# AKA-BeagleBone-ProtoBoard-v0_1.net
KiCad netlist of a schematic drawn in EAGLE
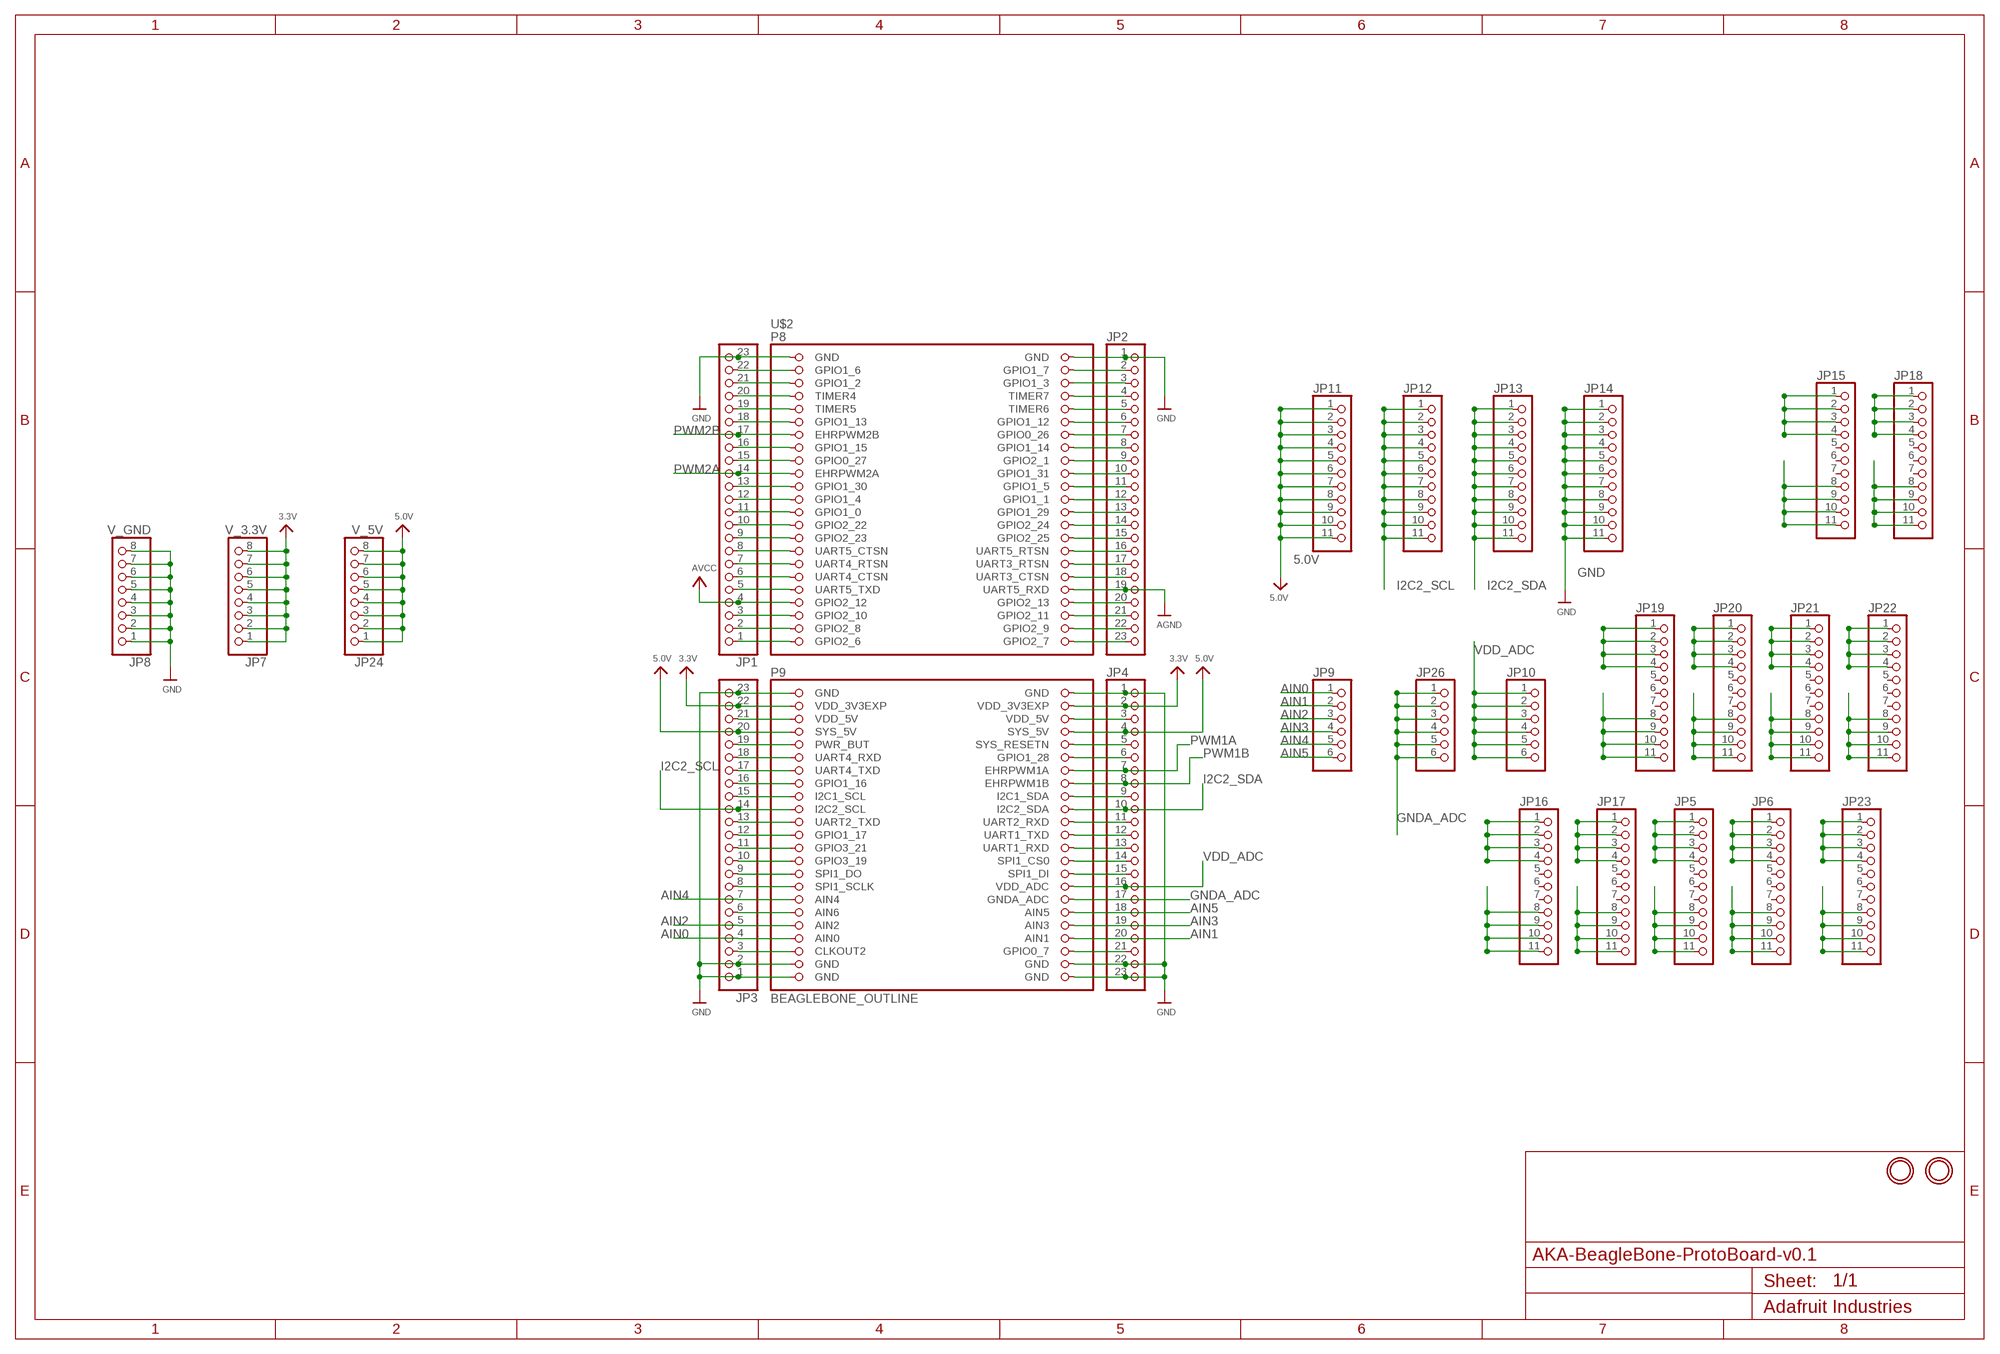
[diagram p0: schematic, sheet 1]

(export (version "E")
  (design (tool "Eeschema 10.0.6"))
  (components
    (comp (ref "JP1")
      (value "HEADER-1X23")
      (footprint "eagle-import:1X23_ROUND_70MIL")
      (libsource (lib "eagle-import") (part "HEADER-1X23"))
    )
    (comp (ref "JP2")
      (value "HEADER-1X23")
      (footprint "eagle-import:1X23_ROUND_70MIL")
      (libsource (lib "eagle-import") (part "HEADER-1X23"))
    )
    (comp (ref "JP3")
      (value "HEADER-1X23")
      (footprint "eagle-import:1X23_ROUND_70MIL")
      (libsource (lib "eagle-import") (part "HEADER-1X23"))
    )
    (comp (ref "JP4")
      (value "HEADER-1X23")
      (footprint "eagle-import:1X23_ROUND_70MIL")
      (libsource (lib "eagle-import") (part "HEADER-1X23"))
    )
    (comp (ref "JP5")
      (value "HEADER-1X1176MIL")
      (footprint "eagle-import:1X11_ROUND_76")
      (libsource (lib "eagle-import") (part "HEADER-1X1176MIL"))
    )
    (comp (ref "JP6")
      (value "HEADER-1X1176MIL")
      (footprint "eagle-import:1X11_ROUND_76")
      (libsource (lib "eagle-import") (part "HEADER-1X1176MIL"))
    )
    (comp (ref "JP7")
      (value "V_3.3V")
      (footprint "eagle-import:1X08_ROUND_70")
      (libsource (lib "eagle-import") (part "HEADER-1X870MIL"))
    )
    (comp (ref "JP8")
      (value "V_GND")
      (footprint "eagle-import:1X08_ROUND_70")
      (libsource (lib "eagle-import") (part "HEADER-1X870MIL"))
    )
    (comp (ref "JP9")
      (value "HEADER-1X676MIL")
      (footprint "eagle-import:1X06_ROUND_76")
      (libsource (lib "eagle-import") (part "HEADER-1X676MIL"))
    )
    (comp (ref "JP10")
      (value "HEADER-1X676MIL")
      (footprint "eagle-import:1X06_ROUND_76")
      (libsource (lib "eagle-import") (part "HEADER-1X676MIL"))
    )
    (comp (ref "JP11")
      (value "HEADER-1X1176MIL")
      (footprint "eagle-import:1X11_ROUND_76")
      (libsource (lib "eagle-import") (part "HEADER-1X1176MIL"))
    )
    (comp (ref "JP12")
      (value "HEADER-1X1176MIL")
      (footprint "eagle-import:1X11_ROUND_76")
      (libsource (lib "eagle-import") (part "HEADER-1X1176MIL"))
    )
    (comp (ref "JP13")
      (value "HEADER-1X1176MIL")
      (footprint "eagle-import:1X11_ROUND_76")
      (libsource (lib "eagle-import") (part "HEADER-1X1176MIL"))
    )
    (comp (ref "JP14")
      (value "HEADER-1X1176MIL")
      (footprint "eagle-import:1X11_ROUND_76")
      (libsource (lib "eagle-import") (part "HEADER-1X1176MIL"))
    )
    (comp (ref "JP15")
      (value "HEADER-1X1176MIL")
      (footprint "eagle-import:1X11_ROUND_76")
      (libsource (lib "eagle-import") (part "HEADER-1X1176MIL"))
    )
    (comp (ref "JP16")
      (value "HEADER-1X1176MIL")
      (footprint "eagle-import:1X11_ROUND_76")
      (libsource (lib "eagle-import") (part "HEADER-1X1176MIL"))
    )
    (comp (ref "JP17")
      (value "HEADER-1X1176MIL")
      (footprint "eagle-import:1X11_ROUND_76")
      (libsource (lib "eagle-import") (part "HEADER-1X1176MIL"))
    )
    (comp (ref "JP18")
      (value "HEADER-1X1176MIL")
      (footprint "eagle-import:1X11_ROUND_76")
      (libsource (lib "eagle-import") (part "HEADER-1X1176MIL"))
    )
    (comp (ref "JP19")
      (value "HEADER-1X1176MIL")
      (footprint "eagle-import:1X11_ROUND_76")
      (libsource (lib "eagle-import") (part "HEADER-1X1176MIL"))
    )
    (comp (ref "JP20")
      (value "HEADER-1X1176MIL")
      (footprint "eagle-import:1X11_ROUND_76")
      (libsource (lib "eagle-import") (part "HEADER-1X1176MIL"))
    )
    (comp (ref "JP21")
      (value "HEADER-1X1176MIL")
      (footprint "eagle-import:1X11_ROUND_76")
      (libsource (lib "eagle-import") (part "HEADER-1X1176MIL"))
    )
    (comp (ref "JP22")
      (value "HEADER-1X1176MIL")
      (footprint "eagle-import:1X11_ROUND_76")
      (libsource (lib "eagle-import") (part "HEADER-1X1176MIL"))
    )
    (comp (ref "JP23")
      (value "HEADER-1X1176MIL")
      (footprint "eagle-import:1X11_ROUND_76")
      (libsource (lib "eagle-import") (part "HEADER-1X1176MIL"))
    )
    (comp (ref "JP24")
      (value "V_5V")
      (footprint "eagle-import:1X08_ROUND_70")
      (libsource (lib "eagle-import") (part "HEADER-1X870MIL"))
    )
    (comp (ref "JP26")
      (value "HEADER-1X676MIL")
      (footprint "eagle-import:1X06_ROUND_76")
      (libsource (lib "eagle-import") (part "HEADER-1X676MIL"))
    )
    (comp (ref "U$2")
      (value "BEAGLEBONE_OUTLINE")
      (footprint "eagle-import:BEAGLEBONE_SHIELD")
      (libsource (lib "eagle-import") (part "BEAGLEBONE_OUTLINE"))
    )
    (comp (ref "U$22")
      (value "MOUNTINGHOLE3.0THIN")
      (footprint "eagle-import:MOUNTINGHOLE_3.0_PLATEDTHIN")
      (libsource (lib "eagle-import") (part "MOUNTINGHOLE3.0THIN"))
    )
    (comp (ref "U$23")
      (value "MOUNTINGHOLE3.0THIN")
      (footprint "eagle-import:MOUNTINGHOLE_3.0_PLATEDTHIN")
      (libsource (lib "eagle-import") (part "MOUNTINGHOLE3.0THIN"))
    )
  )
  (nets
    (net (code "1") (name "/AIN0") (class "Default")
      (node (ref "JP3") (pin "4") (pinfunction "4_4") (pintype "passive"))
      (node (ref "JP9") (pin "1") (pinfunction "1_1") (pintype "passive"))
      (node (ref "U$2") (pin "85") (pinfunction "AIN0_85") (pintype "power_in"))
    )
    (net (code "2") (name "/AIN1") (class "Default")
      (node (ref "JP4") (pin "20") (pinfunction "20_20") (pintype "passive"))
      (node (ref "JP9") (pin "2") (pinfunction "2_2") (pintype "passive"))
      (node (ref "U$2") (pin "86") (pinfunction "AIN1_86") (pintype "input"))
    )
    (net (code "3") (name "/AIN2") (class "Default")
      (node (ref "JP3") (pin "5") (pinfunction "5_5") (pintype "passive"))
      (node (ref "JP9") (pin "3") (pinfunction "3_3") (pintype "passive"))
      (node (ref "U$2") (pin "83") (pinfunction "AIN2_83") (pintype "passive"))
    )
    (net (code "4") (name "/AIN3") (class "Default")
      (node (ref "JP4") (pin "19") (pinfunction "19_19") (pintype "passive"))
      (node (ref "JP9") (pin "4") (pinfunction "4_4") (pintype "passive"))
      (node (ref "U$2") (pin "84") (pinfunction "AIN3_84") (pintype "power_in"))
    )
    (net (code "5") (name "/AIN4") (class "Default")
      (node (ref "JP3") (pin "7") (pinfunction "7_7") (pintype "passive"))
      (node (ref "JP9") (pin "5") (pinfunction "5_5") (pintype "passive"))
      (node (ref "U$2") (pin "79") (pinfunction "AIN4_79") (pintype "passive"))
    )
    (net (code "6") (name "/AIN5") (class "Default")
      (node (ref "JP4") (pin "18") (pinfunction "18_18") (pintype "passive"))
      (node (ref "JP9") (pin "6") (pinfunction "6_6") (pintype "passive"))
      (node (ref "U$2") (pin "82") (pinfunction "AIN5_82") (pintype "passive"))
    )
    (net (code "7") (name "/GNDA_ADC") (class "Default")
      (node (ref "JP26") (pin "1") (pinfunction "1_1") (pintype "passive"))
      (node (ref "JP26") (pin "2") (pinfunction "2_2") (pintype "passive"))
      (node (ref "JP26") (pin "3") (pinfunction "3_3") (pintype "passive"))
      (node (ref "JP26") (pin "4") (pinfunction "4_4") (pintype "passive"))
      (node (ref "JP26") (pin "5") (pinfunction "5_5") (pintype "passive"))
      (node (ref "JP26") (pin "6") (pinfunction "6_6") (pintype "passive"))
      (node (ref "JP4") (pin "17") (pinfunction "17_17") (pintype "passive"))
      (node (ref "U$2") (pin "80") (pinfunction "GNDA_ADC_80") (pintype "passive"))
    )
    (net (code "8") (name "/I2C2_SCL") (class "Default")
      (node (ref "JP12") (pin "1") (pinfunction "1_1") (pintype "passive"))
      (node (ref "JP12") (pin "10") (pinfunction "10_10") (pintype "passive"))
      (node (ref "JP12") (pin "11") (pinfunction "11_11") (pintype "passive"))
      (node (ref "JP12") (pin "2") (pinfunction "2_2") (pintype "passive"))
      (node (ref "JP12") (pin "3") (pinfunction "3_3") (pintype "passive"))
      (node (ref "JP12") (pin "4") (pinfunction "4_4") (pintype "passive"))
      (node (ref "JP12") (pin "5") (pinfunction "5_5") (pintype "passive"))
      (node (ref "JP12") (pin "6") (pinfunction "6_6") (pintype "passive"))
      (node (ref "JP12") (pin "7") (pinfunction "7_7") (pintype "passive"))
      (node (ref "JP12") (pin "8") (pinfunction "8_8") (pintype "passive"))
      (node (ref "JP12") (pin "9") (pinfunction "9_9") (pintype "passive"))
      (node (ref "JP3") (pin "14") (pinfunction "14_14") (pintype "passive"))
      (node (ref "U$2") (pin "65") (pinfunction "I2C2_SCL_65") (pintype "passive"))
    )
    (net (code "9") (name "/I2C2_SDA") (class "Default")
      (node (ref "JP13") (pin "1") (pinfunction "1_1") (pintype "passive"))
      (node (ref "JP13") (pin "10") (pinfunction "10_10") (pintype "passive"))
      (node (ref "JP13") (pin "11") (pinfunction "11_11") (pintype "passive"))
      (node (ref "JP13") (pin "2") (pinfunction "2_2") (pintype "passive"))
      (node (ref "JP13") (pin "3") (pinfunction "3_3") (pintype "passive"))
      (node (ref "JP13") (pin "4") (pinfunction "4_4") (pintype "passive"))
      (node (ref "JP13") (pin "5") (pinfunction "5_5") (pintype "passive"))
      (node (ref "JP13") (pin "6") (pinfunction "6_6") (pintype "passive"))
      (node (ref "JP13") (pin "7") (pinfunction "7_7") (pintype "passive"))
      (node (ref "JP13") (pin "8") (pinfunction "8_8") (pintype "passive"))
      (node (ref "JP13") (pin "9") (pinfunction "9_9") (pintype "passive"))
      (node (ref "JP4") (pin "10") (pinfunction "10_10") (pintype "passive"))
      (node (ref "U$2") (pin "66") (pinfunction "I2C2_SDA_66") (pintype "passive"))
    )
    (net (code "10") (name "/PWM1A") (class "Default")
      (node (ref "JP4") (pin "7") (pinfunction "7_7") (pintype "passive"))
      (node (ref "U$2") (pin "60") (pinfunction "EHRPWM1A_60") (pintype "passive"))
    )
    (net (code "11") (name "/PWM1B") (class "Default")
      (node (ref "JP4") (pin "8") (pinfunction "8_8") (pintype "passive"))
      (node (ref "U$2") (pin "62") (pinfunction "EHRPWM1B_62") (pintype "passive"))
    )
    (net (code "12") (name "/PWM2A") (class "Default")
      (node (ref "JP1") (pin "14") (pinfunction "14_14") (pintype "passive"))
      (node (ref "JP18") (pin "10") (pinfunction "10_10") (pintype "passive"))
      (node (ref "JP18") (pin "11") (pinfunction "11_11") (pintype "passive"))
      (node (ref "JP18") (pin "8") (pinfunction "8_8") (pintype "passive"))
      (node (ref "JP18") (pin "9") (pinfunction "9_9") (pintype "passive"))
      (node (ref "U$2") (pin "19") (pinfunction "EHRPWM2A_19") (pintype "passive"))
    )
    (net (code "13") (name "/PWM2B") (class "Default")
      (node (ref "JP1") (pin "17") (pinfunction "17_17") (pintype "passive"))
      (node (ref "JP15") (pin "10") (pinfunction "10_10") (pintype "passive"))
      (node (ref "JP15") (pin "11") (pinfunction "11_11") (pintype "passive"))
      (node (ref "JP15") (pin "8") (pinfunction "8_8") (pintype "passive"))
      (node (ref "JP15") (pin "9") (pinfunction "9_9") (pintype "passive"))
      (node (ref "U$2") (pin "13") (pinfunction "EHRPWM2B_13") (pintype "passive"))
    )
    (net (code "14") (name "/VDD_ADC") (class "Default")
      (node (ref "JP10") (pin "1") (pinfunction "1_1") (pintype "passive"))
      (node (ref "JP10") (pin "2") (pinfunction "2_2") (pintype "passive"))
      (node (ref "JP10") (pin "3") (pinfunction "3_3") (pintype "passive"))
      (node (ref "JP10") (pin "4") (pinfunction "4_4") (pintype "passive"))
      (node (ref "JP10") (pin "5") (pinfunction "5_5") (pintype "passive"))
      (node (ref "JP10") (pin "6") (pinfunction "6_6") (pintype "passive"))
      (node (ref "JP4") (pin "16") (pinfunction "16_16") (pintype "passive"))
      (node (ref "U$2") (pin "78") (pinfunction "VDD_ADC_78") (pintype "passive"))
    )
    (net (code "15") (name "3.3V") (class "Default")
      (node (ref "JP3") (pin "22") (pinfunction "22_22") (pintype "passive"))
      (node (ref "JP4") (pin "2") (pinfunction "2_2") (pintype "passive"))
      (node (ref "JP7") (pin "1") (pinfunction "1_1") (pintype "passive"))
      (node (ref "JP7") (pin "2") (pinfunction "2_2") (pintype "passive"))
      (node (ref "JP7") (pin "3") (pinfunction "3_3") (pintype "passive"))
      (node (ref "JP7") (pin "4") (pinfunction "4_4") (pintype "passive"))
      (node (ref "JP7") (pin "5") (pinfunction "5_5") (pintype "passive"))
      (node (ref "JP7") (pin "6") (pinfunction "6_6") (pintype "passive"))
      (node (ref "JP7") (pin "7") (pinfunction "7_7") (pintype "passive"))
      (node (ref "JP7") (pin "8") (pinfunction "8_8") (pintype "passive"))
      (node (ref "U$2") (pin "49") (pinfunction "VDD_3V3EXP_49") (pintype "power_in"))
      (node (ref "U$2") (pin "50") (pinfunction "VDD_3V3EXP_50") (pintype "power_in"))
    )
    (net (code "16") (name "5.0V") (class "Default")
      (node (ref "JP11") (pin "1") (pinfunction "1_1") (pintype "passive"))
      (node (ref "JP11") (pin "10") (pinfunction "10_10") (pintype "passive"))
      (node (ref "JP11") (pin "11") (pinfunction "11_11") (pintype "passive"))
      (node (ref "JP11") (pin "2") (pinfunction "2_2") (pintype "passive"))
      (node (ref "JP11") (pin "3") (pinfunction "3_3") (pintype "passive"))
      (node (ref "JP11") (pin "4") (pinfunction "4_4") (pintype "passive"))
      (node (ref "JP11") (pin "5") (pinfunction "5_5") (pintype "passive"))
      (node (ref "JP11") (pin "6") (pinfunction "6_6") (pintype "passive"))
      (node (ref "JP11") (pin "7") (pinfunction "7_7") (pintype "passive"))
      (node (ref "JP11") (pin "8") (pinfunction "8_8") (pintype "passive"))
      (node (ref "JP11") (pin "9") (pinfunction "9_9") (pintype "passive"))
      (node (ref "JP24") (pin "1") (pinfunction "1_1") (pintype "passive"))
      (node (ref "JP24") (pin "2") (pinfunction "2_2") (pintype "passive"))
      (node (ref "JP24") (pin "3") (pinfunction "3_3") (pintype "passive"))
      (node (ref "JP24") (pin "4") (pinfunction "4_4") (pintype "passive"))
      (node (ref "JP24") (pin "5") (pinfunction "5_5") (pintype "passive"))
      (node (ref "JP24") (pin "6") (pinfunction "6_6") (pintype "passive"))
      (node (ref "JP24") (pin "7") (pinfunction "7_7") (pintype "passive"))
      (node (ref "JP24") (pin "8") (pinfunction "8_8") (pintype "passive"))
      (node (ref "JP3") (pin "20") (pinfunction "20_20") (pintype "passive"))
      (node (ref "JP4") (pin "4") (pinfunction "4_4") (pintype "passive"))
      (node (ref "U$2") (pin "53") (pinfunction "SYS_5V_53") (pintype "passive"))
      (node (ref "U$2") (pin "54") (pinfunction "SYS_5V_54") (pintype "passive"))
    )
    (net (code "17") (name "AGND") (class "Default")
      (node (ref "JP2") (pin "19") (pinfunction "19_19") (pintype "passive"))
      (node (ref "U$2") (pin "38") (pinfunction "UART5_RXD_38") (pintype "passive"))
    )
    (net (code "18") (name "AVCC") (class "Default")
      (node (ref "JP1") (pin "4") (pinfunction "4_4") (pintype "passive"))
      (node (ref "U$2") (pin "39") (pinfunction "GPIO2_12_39") (pintype "passive"))
    )
    (net (code "19") (name "GND") (class "Default")
      (node (ref "JP1") (pin "23") (pinfunction "23_23") (pintype "passive"))
      (node (ref "JP14") (pin "1") (pinfunction "1_1") (pintype "passive"))
      (node (ref "JP14") (pin "10") (pinfunction "10_10") (pintype "passive"))
      (node (ref "JP14") (pin "11") (pinfunction "11_11") (pintype "passive"))
      (node (ref "JP14") (pin "2") (pinfunction "2_2") (pintype "passive"))
      (node (ref "JP14") (pin "3") (pinfunction "3_3") (pintype "passive"))
      (node (ref "JP14") (pin "4") (pinfunction "4_4") (pintype "passive"))
      (node (ref "JP14") (pin "5") (pinfunction "5_5") (pintype "passive"))
      (node (ref "JP14") (pin "6") (pinfunction "6_6") (pintype "passive"))
      (node (ref "JP14") (pin "7") (pinfunction "7_7") (pintype "passive"))
      (node (ref "JP14") (pin "8") (pinfunction "8_8") (pintype "passive"))
      (node (ref "JP14") (pin "9") (pinfunction "9_9") (pintype "passive"))
      (node (ref "JP2") (pin "1") (pinfunction "1_1") (pintype "passive"))
      (node (ref "JP3") (pin "1") (pinfunction "1_1") (pintype "passive"))
      (node (ref "JP3") (pin "2") (pinfunction "2_2") (pintype "passive"))
      (node (ref "JP3") (pin "23") (pinfunction "23_23") (pintype "passive"))
      (node (ref "JP4") (pin "1") (pinfunction "1_1") (pintype "passive"))
      (node (ref "JP4") (pin "22") (pinfunction "22_22") (pintype "passive"))
      (node (ref "JP4") (pin "23") (pinfunction "23_23") (pintype "passive"))
      (node (ref "JP8") (pin "1") (pinfunction "1_1") (pintype "passive"))
      (node (ref "JP8") (pin "2") (pinfunction "2_2") (pintype "passive"))
      (node (ref "JP8") (pin "3") (pinfunction "3_3") (pintype "passive"))
      (node (ref "JP8") (pin "4") (pinfunction "4_4") (pintype "passive"))
      (node (ref "JP8") (pin "5") (pinfunction "5_5") (pintype "passive"))
      (node (ref "JP8") (pin "6") (pinfunction "6_6") (pintype "passive"))
      (node (ref "JP8") (pin "7") (pinfunction "7_7") (pintype "passive"))
      (node (ref "JP8") (pin "8") (pinfunction "8_8") (pintype "passive"))
      (node (ref "U$2") (pin "1") (pinfunction "GND_1") (pintype "power_in"))
      (node (ref "U$2") (pin "2") (pinfunction "GND_2") (pintype "power_in"))
      (node (ref "U$2") (pin "47") (pinfunction "GND_47") (pintype "power_in"))
      (node (ref "U$2") (pin "48") (pinfunction "GND_48") (pintype "power_in"))
      (node (ref "U$2") (pin "89") (pinfunction "GND_89") (pintype "input"))
      (node (ref "U$2") (pin "90") (pinfunction "GND_90") (pintype "input"))
      (node (ref "U$2") (pin "91") (pinfunction "GND_91") (pintype "input"))
      (node (ref "U$2") (pin "92") (pinfunction "GND_92") (pintype "input"))
    )
    (net (code "20") (name "Net-(JP3-Pad21)") (class "Default")
      (node (ref "JP3") (pin "21") (pinfunction "21_21") (pintype "passive"))
      (node (ref "U$2") (pin "51") (pinfunction "VDD_5V_51") (pintype "power_in"))
    )
    (net (code "21") (name "Net-(JP4-Pad3)") (class "Default")
      (node (ref "JP4") (pin "3") (pinfunction "3_3") (pintype "passive"))
      (node (ref "U$2") (pin "52") (pinfunction "VDD_5V_52") (pintype "power_in"))
    )
    (net (code "22") (name "Net-(JP5-Pad1)") (class "Default")
      (node (ref "JP5") (pin "1") (pinfunction "1_1") (pintype "passive"))
      (node (ref "JP5") (pin "2") (pinfunction "2_2") (pintype "passive"))
      (node (ref "JP5") (pin "3") (pinfunction "3_3") (pintype "passive"))
      (node (ref "JP5") (pin "4") (pinfunction "4_4") (pintype "passive"))
    )
    (net (code "23") (name "Net-(JP5-Pad10)") (class "Default")
      (node (ref "JP5") (pin "10") (pinfunction "10_10") (pintype "passive"))
      (node (ref "JP5") (pin "11") (pinfunction "11_11") (pintype "passive"))
      (node (ref "JP5") (pin "8") (pinfunction "8_8") (pintype "passive"))
      (node (ref "JP5") (pin "9") (pinfunction "9_9") (pintype "passive"))
    )
    (net (code "24") (name "Net-(JP6-Pad1)") (class "Default")
      (node (ref "JP6") (pin "1") (pinfunction "1_1") (pintype "passive"))
      (node (ref "JP6") (pin "2") (pinfunction "2_2") (pintype "passive"))
      (node (ref "JP6") (pin "3") (pinfunction "3_3") (pintype "passive"))
      (node (ref "JP6") (pin "4") (pinfunction "4_4") (pintype "passive"))
    )
    (net (code "25") (name "Net-(JP6-Pad10)") (class "Default")
      (node (ref "JP6") (pin "10") (pinfunction "10_10") (pintype "passive"))
      (node (ref "JP6") (pin "11") (pinfunction "11_11") (pintype "passive"))
      (node (ref "JP6") (pin "8") (pinfunction "8_8") (pintype "passive"))
      (node (ref "JP6") (pin "9") (pinfunction "9_9") (pintype "passive"))
    )
    (net (code "26") (name "Net-(JP15-Pad1)") (class "Default")
      (node (ref "JP15") (pin "1") (pinfunction "1_1") (pintype "passive"))
      (node (ref "JP15") (pin "2") (pinfunction "2_2") (pintype "passive"))
      (node (ref "JP15") (pin "3") (pinfunction "3_3") (pintype "passive"))
      (node (ref "JP15") (pin "4") (pinfunction "4_4") (pintype "passive"))
    )
    (net (code "27") (name "Net-(JP16-Pad1)") (class "Default")
      (node (ref "JP16") (pin "1") (pinfunction "1_1") (pintype "passive"))
      (node (ref "JP16") (pin "2") (pinfunction "2_2") (pintype "passive"))
      (node (ref "JP16") (pin "3") (pinfunction "3_3") (pintype "passive"))
      (node (ref "JP16") (pin "4") (pinfunction "4_4") (pintype "passive"))
    )
    (net (code "28") (name "Net-(JP16-Pad10)") (class "Default")
      (node (ref "JP16") (pin "10") (pinfunction "10_10") (pintype "passive"))
      (node (ref "JP16") (pin "11") (pinfunction "11_11") (pintype "passive"))
      (node (ref "JP16") (pin "8") (pinfunction "8_8") (pintype "passive"))
      (node (ref "JP16") (pin "9") (pinfunction "9_9") (pintype "passive"))
    )
    (net (code "29") (name "Net-(JP17-Pad1)") (class "Default")
      (node (ref "JP17") (pin "1") (pinfunction "1_1") (pintype "passive"))
      (node (ref "JP17") (pin "2") (pinfunction "2_2") (pintype "passive"))
      (node (ref "JP17") (pin "3") (pinfunction "3_3") (pintype "passive"))
      (node (ref "JP17") (pin "4") (pinfunction "4_4") (pintype "passive"))
    )
    (net (code "30") (name "Net-(JP17-Pad10)") (class "Default")
      (node (ref "JP17") (pin "10") (pinfunction "10_10") (pintype "passive"))
      (node (ref "JP17") (pin "11") (pinfunction "11_11") (pintype "passive"))
      (node (ref "JP17") (pin "8") (pinfunction "8_8") (pintype "passive"))
      (node (ref "JP17") (pin "9") (pinfunction "9_9") (pintype "passive"))
    )
    (net (code "31") (name "Net-(JP18-Pad1)") (class "Default")
      (node (ref "JP18") (pin "1") (pinfunction "1_1") (pintype "passive"))
      (node (ref "JP18") (pin "2") (pinfunction "2_2") (pintype "passive"))
      (node (ref "JP18") (pin "3") (pinfunction "3_3") (pintype "passive"))
      (node (ref "JP18") (pin "4") (pinfunction "4_4") (pintype "passive"))
    )
    (net (code "32") (name "Net-(JP19-Pad1)") (class "Default")
      (node (ref "JP19") (pin "1") (pinfunction "1_1") (pintype "passive"))
      (node (ref "JP19") (pin "2") (pinfunction "2_2") (pintype "passive"))
      (node (ref "JP19") (pin "3") (pinfunction "3_3") (pintype "passive"))
      (node (ref "JP19") (pin "4") (pinfunction "4_4") (pintype "passive"))
    )
    (net (code "33") (name "Net-(JP19-Pad10)") (class "Default")
      (node (ref "JP19") (pin "10") (pinfunction "10_10") (pintype "passive"))
      (node (ref "JP19") (pin "11") (pinfunction "11_11") (pintype "passive"))
      (node (ref "JP19") (pin "8") (pinfunction "8_8") (pintype "passive"))
      (node (ref "JP19") (pin "9") (pinfunction "9_9") (pintype "passive"))
    )
    (net (code "34") (name "Net-(JP20-Pad1)") (class "Default")
      (node (ref "JP20") (pin "1") (pinfunction "1_1") (pintype "passive"))
      (node (ref "JP20") (pin "2") (pinfunction "2_2") (pintype "passive"))
      (node (ref "JP20") (pin "3") (pinfunction "3_3") (pintype "passive"))
      (node (ref "JP20") (pin "4") (pinfunction "4_4") (pintype "passive"))
    )
    (net (code "35") (name "Net-(JP20-Pad10)") (class "Default")
      (node (ref "JP20") (pin "10") (pinfunction "10_10") (pintype "passive"))
      (node (ref "JP20") (pin "11") (pinfunction "11_11") (pintype "passive"))
      (node (ref "JP20") (pin "8") (pinfunction "8_8") (pintype "passive"))
      (node (ref "JP20") (pin "9") (pinfunction "9_9") (pintype "passive"))
    )
    (net (code "36") (name "Net-(JP21-Pad1)") (class "Default")
      (node (ref "JP21") (pin "1") (pinfunction "1_1") (pintype "passive"))
      (node (ref "JP21") (pin "2") (pinfunction "2_2") (pintype "passive"))
      (node (ref "JP21") (pin "3") (pinfunction "3_3") (pintype "passive"))
      (node (ref "JP21") (pin "4") (pinfunction "4_4") (pintype "passive"))
    )
    (net (code "37") (name "Net-(JP21-Pad10)") (class "Default")
      (node (ref "JP21") (pin "10") (pinfunction "10_10") (pintype "passive"))
      (node (ref "JP21") (pin "11") (pinfunction "11_11") (pintype "passive"))
      (node (ref "JP21") (pin "8") (pinfunction "8_8") (pintype "passive"))
      (node (ref "JP21") (pin "9") (pinfunction "9_9") (pintype "passive"))
    )
    (net (code "38") (name "Net-(JP22-Pad1)") (class "Default")
      (node (ref "JP22") (pin "1") (pinfunction "1_1") (pintype "passive"))
      (node (ref "JP22") (pin "2") (pinfunction "2_2") (pintype "passive"))
      (node (ref "JP22") (pin "3") (pinfunction "3_3") (pintype "passive"))
      (node (ref "JP22") (pin "4") (pinfunction "4_4") (pintype "passive"))
    )
    (net (code "39") (name "Net-(JP22-Pad10)") (class "Default")
      (node (ref "JP22") (pin "10") (pinfunction "10_10") (pintype "passive"))
      (node (ref "JP22") (pin "11") (pinfunction "11_11") (pintype "passive"))
      (node (ref "JP22") (pin "8") (pinfunction "8_8") (pintype "passive"))
      (node (ref "JP22") (pin "9") (pinfunction "9_9") (pintype "passive"))
    )
    (net (code "40") (name "Net-(JP23-Pad1)") (class "Default")
      (node (ref "JP23") (pin "1") (pinfunction "1_1") (pintype "passive"))
      (node (ref "JP23") (pin "2") (pinfunction "2_2") (pintype "passive"))
      (node (ref "JP23") (pin "3") (pinfunction "3_3") (pintype "passive"))
      (node (ref "JP23") (pin "4") (pinfunction "4_4") (pintype "passive"))
    )
    (net (code "41") (name "Net-(JP23-Pad10)") (class "Default")
      (node (ref "JP23") (pin "10") (pinfunction "10_10") (pintype "passive"))
      (node (ref "JP23") (pin "11") (pinfunction "11_11") (pintype "passive"))
      (node (ref "JP23") (pin "8") (pinfunction "8_8") (pintype "passive"))
      (node (ref "JP23") (pin "9") (pinfunction "9_9") (pintype "passive"))
    )
    (net (code "42") (name "Net-(U$2-AIN6)") (class "Default")
      (node (ref "JP3") (pin "6") (pinfunction "6_6") (pintype "passive"))
      (node (ref "U$2") (pin "81") (pinfunction "AIN6_81") (pintype "passive"))
    )
    (net (code "43") (name "Net-(U$2-CLKOUT2)") (class "Default")
      (node (ref "JP3") (pin "3") (pinfunction "3_3") (pintype "passive"))
      (node (ref "U$2") (pin "87") (pinfunction "CLKOUT2_87") (pintype "input"))
    )
    (net (code "44") (name "Net-(U$2-GPIO0_7)") (class "Default")
      (node (ref "JP4") (pin "21") (pinfunction "21_21") (pintype "passive"))
      (node (ref "U$2") (pin "88") (pinfunction "GPIO0_7_88") (pintype "input"))
    )
    (net (code "45") (name "Net-(U$2-GPIO0_26)") (class "Default")
      (node (ref "JP2") (pin "7") (pinfunction "7_7") (pintype "passive"))
      (node (ref "U$2") (pin "14") (pinfunction "GPIO0_26_14") (pintype "passive"))
    )
    (net (code "46") (name "Net-(U$2-GPIO0_27)") (class "Default")
      (node (ref "JP1") (pin "15") (pinfunction "15_15") (pintype "passive"))
      (node (ref "U$2") (pin "17") (pinfunction "GPIO0_27_17") (pintype "passive"))
    )
    (net (code "47") (name "Net-(U$2-GPIO1_0)") (class "Default")
      (node (ref "JP1") (pin "11") (pinfunction "11_11") (pintype "passive"))
      (node (ref "U$2") (pin "25") (pinfunction "GPIO1_0_25") (pintype "passive"))
    )
    (net (code "48") (name "Net-(U$2-GPIO1_1)") (class "Default")
      (node (ref "JP2") (pin "12") (pinfunction "12_12") (pintype "passive"))
      (node (ref "U$2") (pin "24") (pinfunction "GPIO1_1_24") (pintype "passive"))
    )
    (net (code "49") (name "Net-(U$2-GPIO1_2)") (class "Default")
      (node (ref "JP1") (pin "21") (pinfunction "21_21") (pintype "passive"))
      (node (ref "U$2") (pin "5") (pinfunction "GPIO1_2_5") (pintype "passive"))
    )
    (net (code "50") (name "Net-(U$2-GPIO1_3)") (class "Default")
      (node (ref "JP2") (pin "3") (pinfunction "3_3") (pintype "passive"))
      (node (ref "U$2") (pin "6") (pinfunction "GPIO1_3_6") (pintype "passive"))
    )
    (net (code "51") (name "Net-(U$2-GPIO1_4)") (class "Default")
      (node (ref "JP1") (pin "12") (pinfunction "12_12") (pintype "passive"))
      (node (ref "U$2") (pin "23") (pinfunction "GPIO1_4_23") (pintype "passive"))
    )
    (net (code "52") (name "Net-(U$2-GPIO1_5)") (class "Default")
      (node (ref "JP2") (pin "11") (pinfunction "11_11") (pintype "passive"))
      (node (ref "U$2") (pin "22") (pinfunction "GPIO1_5_22") (pintype "passive"))
    )
    (net (code "53") (name "Net-(U$2-GPIO1_6)") (class "Default")
      (node (ref "JP1") (pin "22") (pinfunction "22_22") (pintype "passive"))
      (node (ref "U$2") (pin "3") (pinfunction "GPIO1_6_3") (pintype "power_in"))
    )
    (net (code "54") (name "Net-(U$2-GPIO1_7)") (class "Default")
      (node (ref "JP2") (pin "2") (pinfunction "2_2") (pintype "passive"))
      (node (ref "U$2") (pin "4") (pinfunction "GPIO1_7_4") (pintype "power_in"))
    )
    (net (code "55") (name "Net-(U$2-GPIO1_12)") (class "Default")
      (node (ref "JP2") (pin "6") (pinfunction "6_6") (pintype "passive"))
      (node (ref "U$2") (pin "12") (pinfunction "GPIO1_12_12") (pintype "passive"))
    )
    (net (code "56") (name "Net-(U$2-GPIO1_13)") (class "Default")
      (node (ref "JP1") (pin "18") (pinfunction "18_18") (pintype "passive"))
      (node (ref "U$2") (pin "11") (pinfunction "GPIO1_13_11") (pintype "passive"))
    )
    (net (code "57") (name "Net-(U$2-GPIO1_14)") (class "Default")
      (node (ref "JP2") (pin "8") (pinfunction "8_8") (pintype "passive"))
      (node (ref "U$2") (pin "16") (pinfunction "GPIO1_14_16") (pintype "passive"))
    )
    (net (code "58") (name "Net-(U$2-GPIO1_15)") (class "Default")
      (node (ref "JP1") (pin "16") (pinfunction "16_16") (pintype "passive"))
      (node (ref "U$2") (pin "15") (pinfunction "GPIO1_15_15") (pintype "passive"))
    )
    (net (code "59") (name "Net-(U$2-GPIO1_16)") (class "Default")
      (node (ref "JP3") (pin "16") (pinfunction "16_16") (pintype "passive"))
      (node (ref "U$2") (pin "61") (pinfunction "GPIO1_16_61") (pintype "passive"))
    )
    (net (code "60") (name "Net-(U$2-GPIO1_17)") (class "Default")
      (node (ref "JP3") (pin "12") (pinfunction "12_12") (pintype "passive"))
      (node (ref "U$2") (pin "69") (pinfunction "GPIO1_17_69") (pintype "passive"))
    )
    (net (code "61") (name "Net-(U$2-GPIO1_28)") (class "Default")
      (node (ref "JP4") (pin "6") (pinfunction "6_6") (pintype "passive"))
      (node (ref "U$2") (pin "58") (pinfunction "GPIO1_28_58") (pintype "passive"))
    )
    (net (code "62") (name "Net-(U$2-GPIO1_29)") (class "Default")
      (node (ref "JP2") (pin "13") (pinfunction "13_13") (pintype "passive"))
      (node (ref "U$2") (pin "26") (pinfunction "GPIO1_29_26") (pintype "passive"))
    )
    (net (code "63") (name "Net-(U$2-GPIO1_30)") (class "Default")
      (node (ref "JP1") (pin "13") (pinfunction "13_13") (pintype "passive"))
      (node (ref "U$2") (pin "21") (pinfunction "GPIO1_30_21") (pintype "passive"))
    )
    (net (code "64") (name "Net-(U$2-GPIO1_31)") (class "Default")
      (node (ref "JP2") (pin "10") (pinfunction "10_10") (pintype "passive"))
      (node (ref "U$2") (pin "20") (pinfunction "GPIO1_31_20") (pintype "passive"))
    )
    (net (code "65") (name "Net-(U$2-GPIO2_1)") (class "Default")
      (node (ref "JP2") (pin "9") (pinfunction "9_9") (pintype "passive"))
      (node (ref "U$2") (pin "18") (pinfunction "GPIO2_1_18") (pintype "passive"))
    )
    (net (code "66") (name "Net-(U$2-GPIO2_6)") (class "Default")
      (node (ref "JP1") (pin "1") (pinfunction "1_1") (pintype "passive"))
      (node (ref "U$2") (pin "45") (pinfunction "GPIO2_6_45") (pintype "power_in"))
    )
    (net (code "67") (name "Net-(U$2-GPIO2_7)") (class "Default")
      (node (ref "JP2") (pin "23") (pinfunction "23_23") (pintype "passive"))
      (node (ref "U$2") (pin "46") (pinfunction "GPIO2_7_46") (pintype "power_in"))
    )
    (net (code "68") (name "Net-(U$2-GPIO2_8)") (class "Default")
      (node (ref "JP1") (pin "2") (pinfunction "2_2") (pintype "passive"))
      (node (ref "U$2") (pin "43") (pinfunction "GPIO2_8_43") (pintype "power_in"))
    )
    (net (code "69") (name "Net-(U$2-GPIO2_9)") (class "Default")
      (node (ref "JP2") (pin "22") (pinfunction "22_22") (pintype "passive"))
      (node (ref "U$2") (pin "44") (pinfunction "GPIO2_9_44") (pintype "power_in"))
    )
    (net (code "70") (name "Net-(U$2-GPIO2_10)") (class "Default")
      (node (ref "JP1") (pin "3") (pinfunction "3_3") (pintype "passive"))
      (node (ref "U$2") (pin "41") (pinfunction "GPIO2_10_41") (pintype "passive"))
    )
    (net (code "71") (name "Net-(U$2-GPIO2_11)") (class "Default")
      (node (ref "JP2") (pin "21") (pinfunction "21_21") (pintype "passive"))
      (node (ref "U$2") (pin "42") (pinfunction "GPIO2_11_42") (pintype "power_in"))
    )
    (net (code "72") (name "Net-(U$2-GPIO2_13)") (class "Default")
      (node (ref "JP2") (pin "20") (pinfunction "20_20") (pintype "passive"))
      (node (ref "U$2") (pin "40") (pinfunction "GPIO2_13_40") (pintype "passive"))
    )
    (net (code "73") (name "Net-(U$2-GPIO2_22)") (class "Default")
      (node (ref "JP1") (pin "10") (pinfunction "10_10") (pintype "passive"))
      (node (ref "U$2") (pin "27") (pinfunction "GPIO2_22_27") (pintype "passive"))
    )
    (net (code "74") (name "Net-(U$2-GPIO2_23)") (class "Default")
      (node (ref "JP1") (pin "9") (pinfunction "9_9") (pintype "passive"))
      (node (ref "U$2") (pin "29") (pinfunction "GPIO2_23_29") (pintype "passive"))
    )
    (net (code "75") (name "Net-(U$2-GPIO2_24)") (class "Default")
      (node (ref "JP2") (pin "14") (pinfunction "14_14") (pintype "passive"))
      (node (ref "U$2") (pin "28") (pinfunction "GPIO2_24_28") (pintype "passive"))
    )
    (net (code "76") (name "Net-(U$2-GPIO2_25)") (class "Default")
      (node (ref "JP2") (pin "15") (pinfunction "15_15") (pintype "passive"))
      (node (ref "U$2") (pin "30") (pinfunction "GPIO2_25_30") (pintype "passive"))
    )
    (net (code "77") (name "Net-(U$2-GPIO3_19)") (class "Default")
      (node (ref "JP3") (pin "10") (pinfunction "10_10") (pintype "passive"))
      (node (ref "U$2") (pin "73") (pinfunction "GPIO3_19_73") (pintype "passive"))
    )
    (net (code "78") (name "Net-(U$2-GPIO3_21)") (class "Default")
      (node (ref "JP3") (pin "11") (pinfunction "11_11") (pintype "passive"))
      (node (ref "U$2") (pin "71") (pinfunction "GPIO3_21_71") (pintype "passive"))
    )
    (net (code "79") (name "Net-(U$2-I2C1_SCL)") (class "Default")
      (node (ref "JP3") (pin "15") (pinfunction "15_15") (pintype "passive"))
      (node (ref "U$2") (pin "63") (pinfunction "I2C1_SCL_63") (pintype "passive"))
    )
    (net (code "80") (name "Net-(U$2-I2C1_SDA)") (class "Default")
      (node (ref "JP4") (pin "9") (pinfunction "9_9") (pintype "passive"))
      (node (ref "U$2") (pin "64") (pinfunction "I2C1_SDA_64") (pintype "passive"))
    )
    (net (code "81") (name "Net-(U$2-PWR_BUT)") (class "Default")
      (node (ref "JP3") (pin "19") (pinfunction "19_19") (pintype "passive"))
      (node (ref "U$2") (pin "55") (pinfunction "PWR_BUT_55") (pintype "passive"))
    )
    (net (code "82") (name "Net-(U$2-SPI1_CS0)") (class "Default")
      (node (ref "JP4") (pin "14") (pinfunction "14_14") (pintype "passive"))
      (node (ref "U$2") (pin "74") (pinfunction "SPI1_CS0_74") (pintype "passive"))
    )
    (net (code "83") (name "Net-(U$2-SPI1_DI)") (class "Default")
      (node (ref "JP4") (pin "15") (pinfunction "15_15") (pintype "passive"))
      (node (ref "U$2") (pin "76") (pinfunction "SPI1_DI_76") (pintype "passive"))
    )
    (net (code "84") (name "Net-(U$2-SPI1_DO)") (class "Default")
      (node (ref "JP3") (pin "9") (pinfunction "9_9") (pintype "passive"))
      (node (ref "U$2") (pin "75") (pinfunction "SPI1_DO_75") (pintype "passive"))
    )
    (net (code "85") (name "Net-(U$2-SPI1_SCLK)") (class "Default")
      (node (ref "JP3") (pin "8") (pinfunction "8_8") (pintype "passive"))
      (node (ref "U$2") (pin "77") (pinfunction "SPI1_SCLK_77") (pintype "passive"))
    )
    (net (code "86") (name "Net-(U$2-SYS_RESETN)") (class "Default")
      (node (ref "JP4") (pin "5") (pinfunction "5_5") (pintype "passive"))
      (node (ref "U$2") (pin "56") (pinfunction "SYS_RESETN_56") (pintype "passive"))
    )
    (net (code "87") (name "Net-(U$2-TIMER4)") (class "Default")
      (node (ref "JP1") (pin "20") (pinfunction "20_20") (pintype "passive"))
      (node (ref "U$2") (pin "7") (pinfunction "TIMER4_7") (pintype "passive"))
    )
    (net (code "88") (name "Net-(U$2-TIMER5)") (class "Default")
      (node (ref "JP1") (pin "19") (pinfunction "19_19") (pintype "passive"))
      (node (ref "U$2") (pin "9") (pinfunction "TIMER5_9") (pintype "passive"))
    )
    (net (code "89") (name "Net-(U$2-TIMER6)") (class "Default")
      (node (ref "JP2") (pin "5") (pinfunction "5_5") (pintype "passive"))
      (node (ref "U$2") (pin "10") (pinfunction "TIMER6_10") (pintype "passive"))
    )
    (net (code "90") (name "Net-(U$2-TIMER7)") (class "Default")
      (node (ref "JP2") (pin "4") (pinfunction "4_4") (pintype "passive"))
      (node (ref "U$2") (pin "8") (pinfunction "TIMER7_8") (pintype "passive"))
    )
    (net (code "91") (name "Net-(U$2-UART1_RXD)") (class "Default")
      (node (ref "JP4") (pin "13") (pinfunction "13_13") (pintype "passive"))
      (node (ref "U$2") (pin "72") (pinfunction "UART1_RXD_72") (pintype "passive"))
    )
    (net (code "92") (name "Net-(U$2-UART1_TXD)") (class "Default")
      (node (ref "JP4") (pin "12") (pinfunction "12_12") (pintype "passive"))
      (node (ref "U$2") (pin "70") (pinfunction "UART1_TXD_70") (pintype "passive"))
    )
    (net (code "93") (name "Net-(U$2-UART2_RXD)") (class "Default")
      (node (ref "JP4") (pin "11") (pinfunction "11_11") (pintype "passive"))
      (node (ref "U$2") (pin "68") (pinfunction "UART2_RXD_68") (pintype "passive"))
    )
    (net (code "94") (name "Net-(U$2-UART2_TXD)") (class "Default")
      (node (ref "JP3") (pin "13") (pinfunction "13_13") (pintype "passive"))
      (node (ref "U$2") (pin "67") (pinfunction "UART2_TXD_67") (pintype "passive"))
    )
    (net (code "95") (name "Net-(U$2-UART3_CTSN)") (class "Default")
      (node (ref "JP2") (pin "18") (pinfunction "18_18") (pintype "passive"))
      (node (ref "U$2") (pin "36") (pinfunction "UART3_CTSN_36") (pintype "passive"))
    )
    (net (code "96") (name "Net-(U$2-UART3_RTSN)") (class "Default")
      (node (ref "JP2") (pin "17") (pinfunction "17_17") (pintype "passive"))
      (node (ref "U$2") (pin "34") (pinfunction "UART3_RTSN_34") (pintype "passive"))
    )
    (net (code "97") (name "Net-(U$2-UART4_CTSN)") (class "Default")
      (node (ref "JP1") (pin "6") (pinfunction "6_6") (pintype "passive"))
      (node (ref "U$2") (pin "35") (pinfunction "UART4_CTSN_35") (pintype "passive"))
    )
    (net (code "98") (name "Net-(U$2-UART4_RTSN)") (class "Default")
      (node (ref "JP1") (pin "7") (pinfunction "7_7") (pintype "passive"))
      (node (ref "U$2") (pin "33") (pinfunction "UART4_RTSN_33") (pintype "passive"))
    )
    (net (code "99") (name "Net-(U$2-UART4_RXD)") (class "Default")
      (node (ref "JP3") (pin "18") (pinfunction "18_18") (pintype "passive"))
      (node (ref "U$2") (pin "57") (pinfunction "UART4_RXD_57") (pintype "passive"))
    )
    (net (code "100") (name "Net-(U$2-UART4_TXD)") (class "Default")
      (node (ref "JP3") (pin "17") (pinfunction "17_17") (pintype "passive"))
      (node (ref "U$2") (pin "59") (pinfunction "UART4_TXD_59") (pintype "passive"))
    )
    (net (code "101") (name "Net-(U$2-UART5_CTSN)") (class "Default")
      (node (ref "JP1") (pin "8") (pinfunction "8_8") (pintype "passive"))
      (node (ref "U$2") (pin "31") (pinfunction "UART5_CTSN_31") (pintype "passive"))
    )
    (net (code "102") (name "Net-(U$2-UART5_RTSN)") (class "Default")
      (node (ref "JP2") (pin "16") (pinfunction "16_16") (pintype "passive"))
      (node (ref "U$2") (pin "32") (pinfunction "UART5_RTSN_32") (pintype "passive"))
    )
    (net (code "103") (name "Net-(U$2-UART5_TXD)") (class "Default")
      (node (ref "JP1") (pin "5") (pinfunction "5_5") (pintype "passive"))
      (node (ref "U$2") (pin "37") (pinfunction "UART5_TXD_37") (pintype "passive"))
    )
    (net (code "104") (name "unconnected-(JP5-Pad5)") (class "Default")
      (node (ref "JP5") (pin "5") (pinfunction "5_5") (pintype "passive"))
    )
    (net (code "105") (name "unconnected-(JP5-Pad6)") (class "Default")
      (node (ref "JP5") (pin "6") (pinfunction "6_6") (pintype "passive"))
    )
    (net (code "106") (name "unconnected-(JP5-Pad7)") (class "Default")
      (node (ref "JP5") (pin "7") (pinfunction "7_7") (pintype "passive"))
    )
    (net (code "107") (name "unconnected-(JP6-Pad5)") (class "Default")
      (node (ref "JP6") (pin "5") (pinfunction "5_5") (pintype "passive"))
    )
    (net (code "108") (name "unconnected-(JP6-Pad6)") (class "Default")
      (node (ref "JP6") (pin "6") (pinfunction "6_6") (pintype "passive"))
    )
    (net (code "109") (name "unconnected-(JP6-Pad7)") (class "Default")
      (node (ref "JP6") (pin "7") (pinfunction "7_7") (pintype "passive"))
    )
    (net (code "110") (name "unconnected-(JP15-Pad5)") (class "Default")
      (node (ref "JP15") (pin "5") (pinfunction "5_5") (pintype "passive"))
    )
    (net (code "111") (name "unconnected-(JP15-Pad6)") (class "Default")
      (node (ref "JP15") (pin "6") (pinfunction "6_6") (pintype "passive"))
    )
    (net (code "112") (name "unconnected-(JP15-Pad7)") (class "Default")
      (node (ref "JP15") (pin "7") (pinfunction "7_7") (pintype "passive"))
    )
    (net (code "113") (name "unconnected-(JP16-Pad5)") (class "Default")
      (node (ref "JP16") (pin "5") (pinfunction "5_5") (pintype "passive"))
    )
    (net (code "114") (name "unconnected-(JP16-Pad6)") (class "Default")
      (node (ref "JP16") (pin "6") (pinfunction "6_6") (pintype "passive"))
    )
    (net (code "115") (name "unconnected-(JP16-Pad7)") (class "Default")
      (node (ref "JP16") (pin "7") (pinfunction "7_7") (pintype "passive"))
    )
    (net (code "116") (name "unconnected-(JP17-Pad5)") (class "Default")
      (node (ref "JP17") (pin "5") (pinfunction "5_5") (pintype "passive"))
    )
    (net (code "117") (name "unconnected-(JP17-Pad6)") (class "Default")
      (node (ref "JP17") (pin "6") (pinfunction "6_6") (pintype "passive"))
    )
    (net (code "118") (name "unconnected-(JP17-Pad7)") (class "Default")
      (node (ref "JP17") (pin "7") (pinfunction "7_7") (pintype "passive"))
    )
    (net (code "119") (name "unconnected-(JP18-Pad5)") (class "Default")
      (node (ref "JP18") (pin "5") (pinfunction "5_5") (pintype "passive"))
    )
    (net (code "120") (name "unconnected-(JP18-Pad6)") (class "Default")
      (node (ref "JP18") (pin "6") (pinfunction "6_6") (pintype "passive"))
    )
    (net (code "121") (name "unconnected-(JP18-Pad7)") (class "Default")
      (node (ref "JP18") (pin "7") (pinfunction "7_7") (pintype "passive"))
    )
    (net (code "122") (name "unconnected-(JP19-Pad5)") (class "Default")
      (node (ref "JP19") (pin "5") (pinfunction "5_5") (pintype "passive"))
    )
    (net (code "123") (name "unconnected-(JP19-Pad6)") (class "Default")
      (node (ref "JP19") (pin "6") (pinfunction "6_6") (pintype "passive"))
    )
    (net (code "124") (name "unconnected-(JP19-Pad7)") (class "Default")
      (node (ref "JP19") (pin "7") (pinfunction "7_7") (pintype "passive"))
    )
    (net (code "125") (name "unconnected-(JP20-Pad5)") (class "Default")
      (node (ref "JP20") (pin "5") (pinfunction "5_5") (pintype "passive"))
    )
    (net (code "126") (name "unconnected-(JP20-Pad6)") (class "Default")
      (node (ref "JP20") (pin "6") (pinfunction "6_6") (pintype "passive"))
    )
    (net (code "127") (name "unconnected-(JP20-Pad7)") (class "Default")
      (node (ref "JP20") (pin "7") (pinfunction "7_7") (pintype "passive"))
    )
    (net (code "128") (name "unconnected-(JP21-Pad5)") (class "Default")
      (node (ref "JP21") (pin "5") (pinfunction "5_5") (pintype "passive"))
    )
    (net (code "129") (name "unconnected-(JP21-Pad6)") (class "Default")
      (node (ref "JP21") (pin "6") (pinfunction "6_6") (pintype "passive"))
    )
    (net (code "130") (name "unconnected-(JP21-Pad7)") (class "Default")
      (node (ref "JP21") (pin "7") (pinfunction "7_7") (pintype "passive"))
    )
    (net (code "131") (name "unconnected-(JP22-Pad5)") (class "Default")
      (node (ref "JP22") (pin "5") (pinfunction "5_5") (pintype "passive"))
    )
    (net (code "132") (name "unconnected-(JP22-Pad6)") (class "Default")
      (node (ref "JP22") (pin "6") (pinfunction "6_6") (pintype "passive"))
    )
    (net (code "133") (name "unconnected-(JP22-Pad7)") (class "Default")
      (node (ref "JP22") (pin "7") (pinfunction "7_7") (pintype "passive"))
    )
    (net (code "134") (name "unconnected-(JP23-Pad5)") (class "Default")
      (node (ref "JP23") (pin "5") (pinfunction "5_5") (pintype "passive"))
    )
    (net (code "135") (name "unconnected-(JP23-Pad6)") (class "Default")
      (node (ref "JP23") (pin "6") (pinfunction "6_6") (pintype "passive"))
    )
    (net (code "136") (name "unconnected-(JP23-Pad7)") (class "Default")
      (node (ref "JP23") (pin "7") (pinfunction "7_7") (pintype "passive"))
    )
  )
)
